# Sheet1.net
KiCad netlist of a schematic drawn in Altium Designer
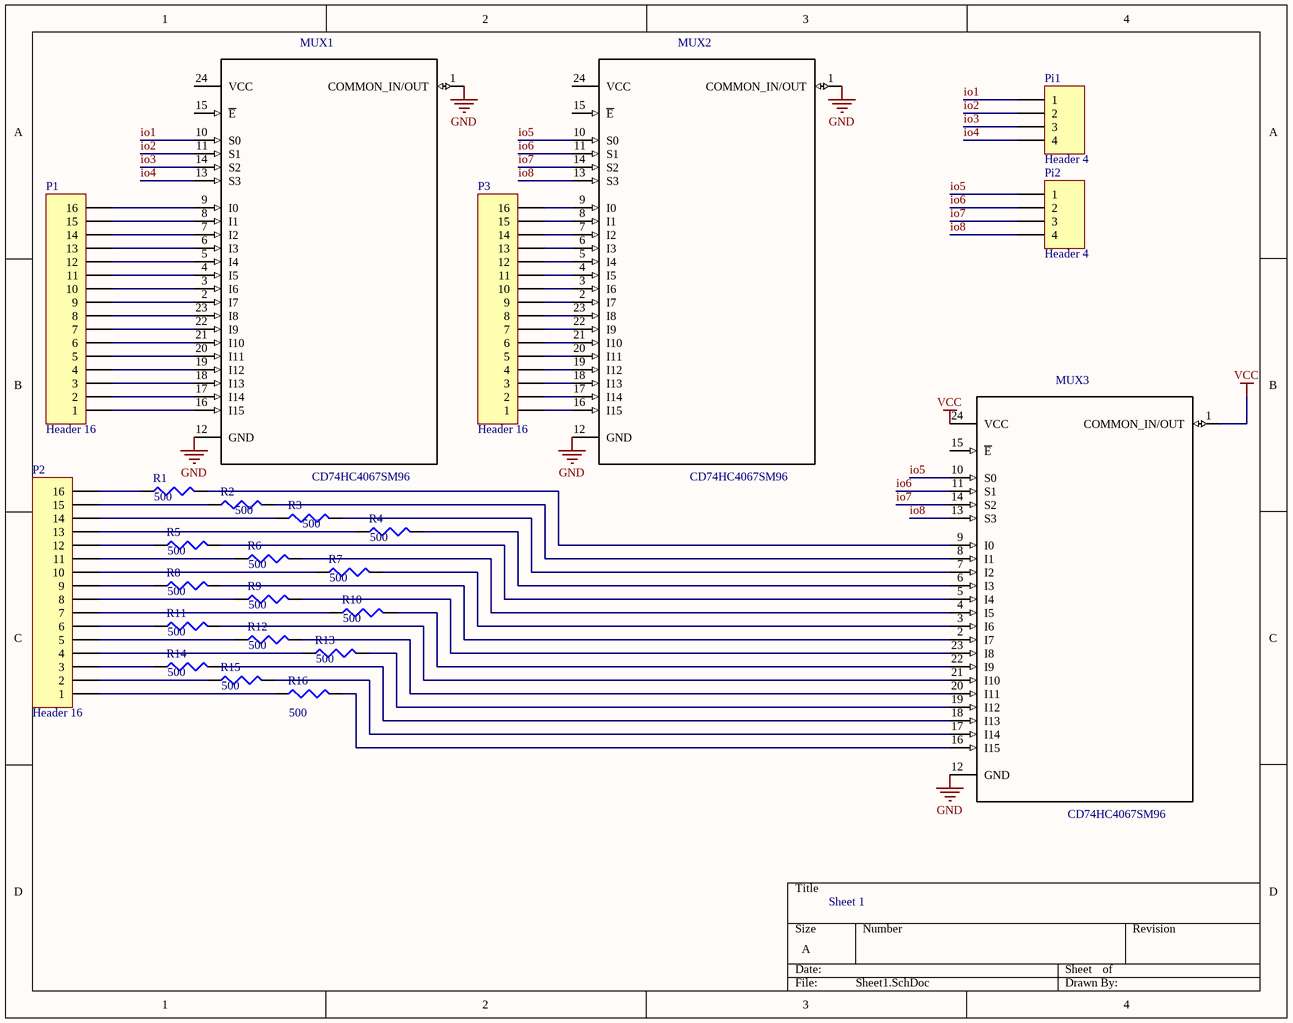
[diagram p0: Sheet1.SchDoc]

(export (version "E")
  (design (tool "Eeschema 10.0.6"))
  (components
    (comp (ref "MUX1")
      (value "CD74HC4067SM96")
      (footprint "SOP65P780X200-24N")
      (description "High Speed CMOS 16-Channel Analog Multiplexer/Demultiplexer 24-SSOP -55 to 125")
      (fields (field (name "MF") "Texas Instruments"))
      (libsource (lib "CD74HC4067SM96") (part "CD74HC4067SM96"))
    )
    (comp (ref "MUX2")
      (value "CD74HC4067SM96")
      (footprint "SOP65P780X200-24N")
      (description "High Speed CMOS 16-Channel Analog Multiplexer/Demultiplexer 24-SSOP -55 to 125")
      (fields (field (name "MF") "Texas Instruments"))
      (libsource (lib "CD74HC4067SM96") (part "CD74HC4067SM96"))
    )
    (comp (ref "MUX3")
      (value "CD74HC4067SM96")
      (footprint "SOP65P780X200-24N")
      (description "High Speed CMOS 16-Channel Analog Multiplexer/Demultiplexer 24-SSOP -55 to 125")
      (fields (field (name "MF") "Texas Instruments"))
      (libsource (lib "CD74HC4067SM96") (part "CD74HC4067SM96"))
    )
    (comp (ref "P1")
      (value "Header 16")
      (footprint "HDR1X16")
      (description "Header, 16-Pin")
      (fields (field (name "PUBLISHER") "Altium Limited"))
      (libsource (lib "Miscellaneous Connectors") (part "Header 16"))
    )
    (comp (ref "P2")
      (value "Header 16")
      (footprint "HDR1X16")
      (description "Header, 16-Pin")
      (fields (field (name "PUBLISHER") "Altium Limited"))
      (libsource (lib "Miscellaneous Connectors") (part "Header 16"))
    )
    (comp (ref "P3")
      (value "Header 16")
      (footprint "HDR1X16")
      (description "Header, 16-Pin")
      (fields (field (name "PUBLISHER") "Altium Limited"))
      (libsource (lib "Miscellaneous Connectors") (part "Header 16"))
    )
    (comp (ref "Pi1")
      (value "Header 4")
      (footprint "HDR1X4")
      (description "Header, 4-Pin")
      (fields (field (name "PUBLISHER") "Altium Limited"))
      (libsource (lib "Miscellaneous Connectors") (part "Header 4"))
    )
    (comp (ref "Pi2")
      (value "Header 4")
      (footprint "HDR1X4")
      (description "Header, 4-Pin")
      (fields (field (name "PUBLISHER") "Altium Limited"))
      (libsource (lib "Miscellaneous Connectors") (part "Header 4"))
    )
    (comp (ref "R1")
      (value "500")
      (footprint "J1-0603")
      (description "Resistor")
      (fields (field (name "Comment") "Res3") (field (name "PUBLISHER") "Altium Limited"))
      (libsource (lib "Miscellaneous Devices") (part "Res3"))
    )
    (comp (ref "R2")
      (value "500")
      (footprint "J1-0603")
      (description "Resistor")
      (fields (field (name "Comment") "Res3") (field (name "PUBLISHER") "Altium Limited"))
      (libsource (lib "Miscellaneous Devices") (part "Res3"))
    )
    (comp (ref "R3")
      (value "500")
      (footprint "J1-0603")
      (description "Resistor")
      (fields (field (name "Comment") "Res3") (field (name "PUBLISHER") "Altium Limited"))
      (libsource (lib "Miscellaneous Devices") (part "Res3"))
    )
    (comp (ref "R4")
      (value "500")
      (footprint "J1-0603")
      (description "Resistor")
      (fields (field (name "Comment") "Res3") (field (name "PUBLISHER") "Altium Limited"))
      (libsource (lib "Miscellaneous Devices") (part "Res3"))
    )
    (comp (ref "R5")
      (value "500")
      (footprint "J1-0603")
      (description "Resistor")
      (fields (field (name "Comment") "Res3") (field (name "PUBLISHER") "Altium Limited"))
      (libsource (lib "Miscellaneous Devices") (part "Res3"))
    )
    (comp (ref "R6")
      (value "500")
      (footprint "J1-0603")
      (description "Resistor")
      (fields (field (name "Comment") "Res3") (field (name "PUBLISHER") "Altium Limited"))
      (libsource (lib "Miscellaneous Devices") (part "Res3"))
    )
    (comp (ref "R7")
      (value "500")
      (footprint "J1-0603")
      (description "Resistor")
      (fields (field (name "Comment") "Res3") (field (name "PUBLISHER") "Altium Limited"))
      (libsource (lib "Miscellaneous Devices") (part "Res3"))
    )
    (comp (ref "R8")
      (value "500")
      (footprint "J1-0603")
      (description "Resistor")
      (fields (field (name "Comment") "Res3") (field (name "PUBLISHER") "Altium Limited"))
      (libsource (lib "Miscellaneous Devices") (part "Res3"))
    )
    (comp (ref "R9")
      (value "500")
      (footprint "J1-0603")
      (description "Resistor")
      (fields (field (name "Comment") "Res3") (field (name "PUBLISHER") "Altium Limited"))
      (libsource (lib "Miscellaneous Devices") (part "Res3"))
    )
    (comp (ref "R10")
      (value "500")
      (footprint "J1-0603")
      (description "Resistor")
      (fields (field (name "Comment") "Res3") (field (name "PUBLISHER") "Altium Limited"))
      (libsource (lib "Miscellaneous Devices") (part "Res3"))
    )
    (comp (ref "R11")
      (value "500")
      (footprint "J1-0603")
      (description "Resistor")
      (fields (field (name "Comment") "Res3") (field (name "PUBLISHER") "Altium Limited"))
      (libsource (lib "Miscellaneous Devices") (part "Res3"))
    )
    (comp (ref "R12")
      (value "500")
      (footprint "J1-0603")
      (description "Resistor")
      (fields (field (name "Comment") "Res3") (field (name "PUBLISHER") "Altium Limited"))
      (libsource (lib "Miscellaneous Devices") (part "Res3"))
    )
    (comp (ref "R13")
      (value "500")
      (footprint "J1-0603")
      (description "Resistor")
      (fields (field (name "Comment") "Res3") (field (name "PUBLISHER") "Altium Limited"))
      (libsource (lib "Miscellaneous Devices") (part "Res3"))
    )
    (comp (ref "R14")
      (value "500")
      (footprint "J1-0603")
      (description "Resistor")
      (fields (field (name "Comment") "Res3") (field (name "PUBLISHER") "Altium Limited"))
      (libsource (lib "Miscellaneous Devices") (part "Res3"))
    )
    (comp (ref "R15")
      (value "500")
      (footprint "J1-0603")
      (description "Resistor")
      (fields (field (name "Comment") "Res3") (field (name "PUBLISHER") "Altium Limited"))
      (libsource (lib "Miscellaneous Devices") (part "Res3"))
    )
    (comp (ref "R16")
      (value "500")
      (footprint "J1-0603")
      (description "Resistor")
      (fields (field (name "Comment") "Res3") (field (name "PUBLISHER") "Altium Limited"))
      (libsource (lib "Miscellaneous Devices") (part "Res3"))
    )
  )
  (nets
    (net (code "1") (name "/io1") (class "Default")
      (node (ref "MUX1") (pin "10") (pinfunction "S0_10") (pintype "input"))
      (node (ref "Pi1") (pin "1") (pinfunction "1_1") (pintype "passive"))
    )
    (net (code "2") (name "/io2") (class "Default")
      (node (ref "MUX1") (pin "11") (pinfunction "S1_11") (pintype "input"))
      (node (ref "Pi1") (pin "2") (pinfunction "2_2") (pintype "passive"))
    )
    (net (code "3") (name "/io3") (class "Default")
      (node (ref "MUX1") (pin "14") (pinfunction "S2_14") (pintype "input"))
      (node (ref "Pi1") (pin "3") (pinfunction "3_3") (pintype "passive"))
    )
    (net (code "4") (name "/io4") (class "Default")
      (node (ref "MUX1") (pin "13") (pinfunction "S3_13") (pintype "input"))
      (node (ref "Pi1") (pin "4") (pinfunction "4_4") (pintype "passive"))
    )
    (net (code "5") (name "/io5") (class "Default")
      (node (ref "MUX2") (pin "10") (pinfunction "S0_10") (pintype "input"))
      (node (ref "MUX3") (pin "10") (pinfunction "S0_10") (pintype "input"))
      (node (ref "Pi2") (pin "1") (pinfunction "1_1") (pintype "passive"))
    )
    (net (code "6") (name "/io6") (class "Default")
      (node (ref "MUX2") (pin "11") (pinfunction "S1_11") (pintype "input"))
      (node (ref "MUX3") (pin "11") (pinfunction "S1_11") (pintype "input"))
      (node (ref "Pi2") (pin "2") (pinfunction "2_2") (pintype "passive"))
    )
    (net (code "7") (name "/io7") (class "Default")
      (node (ref "MUX2") (pin "14") (pinfunction "S2_14") (pintype "input"))
      (node (ref "MUX3") (pin "14") (pinfunction "S2_14") (pintype "input"))
      (node (ref "Pi2") (pin "3") (pinfunction "3_3") (pintype "passive"))
    )
    (net (code "8") (name "/io8") (class "Default")
      (node (ref "MUX2") (pin "13") (pinfunction "S3_13") (pintype "input"))
      (node (ref "MUX3") (pin "13") (pinfunction "S3_13") (pintype "input"))
      (node (ref "Pi2") (pin "4") (pinfunction "4_4") (pintype "passive"))
    )
    (net (code "9") (name "GND") (class "Default")
      (node (ref "MUX1") (pin "1") (pinfunction "COMMON_IN/OUT_1") (pintype "bidirectional"))
      (node (ref "MUX1") (pin "12") (pinfunction "GND_12") (pintype "passive"))
      (node (ref "MUX2") (pin "1") (pinfunction "COMMON_IN/OUT_1") (pintype "bidirectional"))
      (node (ref "MUX2") (pin "12") (pinfunction "GND_12") (pintype "passive"))
      (node (ref "MUX3") (pin "12") (pinfunction "GND_12") (pintype "passive"))
    )
    (net (code "10") (name "Net-(MUX1-I0)") (class "Default")
      (node (ref "MUX1") (pin "9") (pinfunction "I0_9") (pintype "input"))
      (node (ref "P1") (pin "16") (pinfunction "16_16") (pintype "passive"))
    )
    (net (code "11") (name "Net-(MUX1-I1)") (class "Default")
      (node (ref "MUX1") (pin "8") (pinfunction "I1_8") (pintype "input"))
      (node (ref "P1") (pin "15") (pinfunction "15_15") (pintype "passive"))
    )
    (net (code "12") (name "Net-(MUX1-I2)") (class "Default")
      (node (ref "MUX1") (pin "7") (pinfunction "I2_7") (pintype "input"))
      (node (ref "P1") (pin "14") (pinfunction "14_14") (pintype "passive"))
    )
    (net (code "13") (name "Net-(MUX1-I3)") (class "Default")
      (node (ref "MUX1") (pin "6") (pinfunction "I3_6") (pintype "input"))
      (node (ref "P1") (pin "13") (pinfunction "13_13") (pintype "passive"))
    )
    (net (code "14") (name "Net-(MUX1-I4)") (class "Default")
      (node (ref "MUX1") (pin "5") (pinfunction "I4_5") (pintype "input"))
      (node (ref "P1") (pin "12") (pinfunction "12_12") (pintype "passive"))
    )
    (net (code "15") (name "Net-(MUX1-I5)") (class "Default")
      (node (ref "MUX1") (pin "4") (pinfunction "I5_4") (pintype "input"))
      (node (ref "P1") (pin "11") (pinfunction "11_11") (pintype "passive"))
    )
    (net (code "16") (name "Net-(MUX1-I6)") (class "Default")
      (node (ref "MUX1") (pin "3") (pinfunction "I6_3") (pintype "input"))
      (node (ref "P1") (pin "10") (pinfunction "10_10") (pintype "passive"))
    )
    (net (code "17") (name "Net-(MUX1-I7)") (class "Default")
      (node (ref "MUX1") (pin "2") (pinfunction "I7_2") (pintype "input"))
      (node (ref "P1") (pin "9") (pinfunction "9_9") (pintype "passive"))
    )
    (net (code "18") (name "Net-(MUX1-I8)") (class "Default")
      (node (ref "MUX1") (pin "23") (pinfunction "I8_23") (pintype "input"))
      (node (ref "P1") (pin "8") (pinfunction "8_8") (pintype "passive"))
    )
    (net (code "19") (name "Net-(MUX1-I9)") (class "Default")
      (node (ref "MUX1") (pin "22") (pinfunction "I9_22") (pintype "input"))
      (node (ref "P1") (pin "7") (pinfunction "7_7") (pintype "passive"))
    )
    (net (code "20") (name "Net-(MUX1-I10)") (class "Default")
      (node (ref "MUX1") (pin "21") (pinfunction "I10_21") (pintype "input"))
      (node (ref "P1") (pin "6") (pinfunction "6_6") (pintype "passive"))
    )
    (net (code "21") (name "Net-(MUX1-I11)") (class "Default")
      (node (ref "MUX1") (pin "20") (pinfunction "I11_20") (pintype "input"))
      (node (ref "P1") (pin "5") (pinfunction "5_5") (pintype "passive"))
    )
    (net (code "22") (name "Net-(MUX1-I12)") (class "Default")
      (node (ref "MUX1") (pin "19") (pinfunction "I12_19") (pintype "input"))
      (node (ref "P1") (pin "4") (pinfunction "4_4") (pintype "passive"))
    )
    (net (code "23") (name "Net-(MUX1-I13)") (class "Default")
      (node (ref "MUX1") (pin "18") (pinfunction "I13_18") (pintype "input"))
      (node (ref "P1") (pin "3") (pinfunction "3_3") (pintype "passive"))
    )
    (net (code "24") (name "Net-(MUX1-I14)") (class "Default")
      (node (ref "MUX1") (pin "17") (pinfunction "I14_17") (pintype "input"))
      (node (ref "P1") (pin "2") (pinfunction "2_2") (pintype "passive"))
    )
    (net (code "25") (name "Net-(MUX1-I15)") (class "Default")
      (node (ref "MUX1") (pin "16") (pinfunction "I15_16") (pintype "input"))
      (node (ref "P1") (pin "1") (pinfunction "1_1") (pintype "passive"))
    )
    (net (code "26") (name "Net-(MUX2-I0)") (class "Default")
      (node (ref "MUX2") (pin "9") (pinfunction "I0_9") (pintype "input"))
      (node (ref "P3") (pin "16") (pinfunction "16_16") (pintype "passive"))
    )
    (net (code "27") (name "Net-(MUX2-I1)") (class "Default")
      (node (ref "MUX2") (pin "8") (pinfunction "I1_8") (pintype "input"))
      (node (ref "P3") (pin "15") (pinfunction "15_15") (pintype "passive"))
    )
    (net (code "28") (name "Net-(MUX2-I2)") (class "Default")
      (node (ref "MUX2") (pin "7") (pinfunction "I2_7") (pintype "input"))
      (node (ref "P3") (pin "14") (pinfunction "14_14") (pintype "passive"))
    )
    (net (code "29") (name "Net-(MUX2-I3)") (class "Default")
      (node (ref "MUX2") (pin "6") (pinfunction "I3_6") (pintype "input"))
      (node (ref "P3") (pin "13") (pinfunction "13_13") (pintype "passive"))
    )
    (net (code "30") (name "Net-(MUX2-I4)") (class "Default")
      (node (ref "MUX2") (pin "5") (pinfunction "I4_5") (pintype "input"))
      (node (ref "P3") (pin "12") (pinfunction "12_12") (pintype "passive"))
    )
    (net (code "31") (name "Net-(MUX2-I5)") (class "Default")
      (node (ref "MUX2") (pin "4") (pinfunction "I5_4") (pintype "input"))
      (node (ref "P3") (pin "11") (pinfunction "11_11") (pintype "passive"))
    )
    (net (code "32") (name "Net-(MUX2-I6)") (class "Default")
      (node (ref "MUX2") (pin "3") (pinfunction "I6_3") (pintype "input"))
      (node (ref "P3") (pin "10") (pinfunction "10_10") (pintype "passive"))
    )
    (net (code "33") (name "Net-(MUX2-I7)") (class "Default")
      (node (ref "MUX2") (pin "2") (pinfunction "I7_2") (pintype "input"))
      (node (ref "P3") (pin "9") (pinfunction "9_9") (pintype "passive"))
    )
    (net (code "34") (name "Net-(MUX2-I8)") (class "Default")
      (node (ref "MUX2") (pin "23") (pinfunction "I8_23") (pintype "input"))
      (node (ref "P3") (pin "8") (pinfunction "8_8") (pintype "passive"))
    )
    (net (code "35") (name "Net-(MUX2-I9)") (class "Default")
      (node (ref "MUX2") (pin "22") (pinfunction "I9_22") (pintype "input"))
      (node (ref "P3") (pin "7") (pinfunction "7_7") (pintype "passive"))
    )
    (net (code "36") (name "Net-(MUX2-I10)") (class "Default")
      (node (ref "MUX2") (pin "21") (pinfunction "I10_21") (pintype "input"))
      (node (ref "P3") (pin "6") (pinfunction "6_6") (pintype "passive"))
    )
    (net (code "37") (name "Net-(MUX2-I11)") (class "Default")
      (node (ref "MUX2") (pin "20") (pinfunction "I11_20") (pintype "input"))
      (node (ref "P3") (pin "5") (pinfunction "5_5") (pintype "passive"))
    )
    (net (code "38") (name "Net-(MUX2-I12)") (class "Default")
      (node (ref "MUX2") (pin "19") (pinfunction "I12_19") (pintype "input"))
      (node (ref "P3") (pin "4") (pinfunction "4_4") (pintype "passive"))
    )
    (net (code "39") (name "Net-(MUX2-I13)") (class "Default")
      (node (ref "MUX2") (pin "18") (pinfunction "I13_18") (pintype "input"))
      (node (ref "P3") (pin "3") (pinfunction "3_3") (pintype "passive"))
    )
    (net (code "40") (name "Net-(MUX2-I14)") (class "Default")
      (node (ref "MUX2") (pin "17") (pinfunction "I14_17") (pintype "input"))
      (node (ref "P3") (pin "2") (pinfunction "2_2") (pintype "passive"))
    )
    (net (code "41") (name "Net-(MUX2-I15)") (class "Default")
      (node (ref "MUX2") (pin "16") (pinfunction "I15_16") (pintype "input"))
      (node (ref "P3") (pin "1") (pinfunction "1_1") (pintype "passive"))
    )
    (net (code "42") (name "Net-(MUX3-I0)") (class "Default")
      (node (ref "MUX3") (pin "9") (pinfunction "I0_9") (pintype "input"))
      (node (ref "R1") (pin "2") (pinfunction "2_2") (pintype "passive"))
    )
    (net (code "43") (name "Net-(MUX3-I1)") (class "Default")
      (node (ref "MUX3") (pin "8") (pinfunction "I1_8") (pintype "input"))
      (node (ref "R2") (pin "2") (pinfunction "2_2") (pintype "passive"))
    )
    (net (code "44") (name "Net-(MUX3-I2)") (class "Default")
      (node (ref "MUX3") (pin "7") (pinfunction "I2_7") (pintype "input"))
      (node (ref "R3") (pin "2") (pinfunction "2_2") (pintype "passive"))
    )
    (net (code "45") (name "Net-(MUX3-I3)") (class "Default")
      (node (ref "MUX3") (pin "6") (pinfunction "I3_6") (pintype "input"))
      (node (ref "R4") (pin "2") (pinfunction "2_2") (pintype "passive"))
    )
    (net (code "46") (name "Net-(MUX3-I4)") (class "Default")
      (node (ref "MUX3") (pin "5") (pinfunction "I4_5") (pintype "input"))
      (node (ref "R5") (pin "2") (pinfunction "2_2") (pintype "passive"))
    )
    (net (code "47") (name "Net-(MUX3-I5)") (class "Default")
      (node (ref "MUX3") (pin "4") (pinfunction "I5_4") (pintype "input"))
      (node (ref "R6") (pin "2") (pinfunction "2_2") (pintype "passive"))
    )
    (net (code "48") (name "Net-(MUX3-I6)") (class "Default")
      (node (ref "MUX3") (pin "3") (pinfunction "I6_3") (pintype "input"))
      (node (ref "R7") (pin "2") (pinfunction "2_2") (pintype "passive"))
    )
    (net (code "49") (name "Net-(MUX3-I7)") (class "Default")
      (node (ref "MUX3") (pin "2") (pinfunction "I7_2") (pintype "input"))
      (node (ref "R8") (pin "2") (pinfunction "2_2") (pintype "passive"))
    )
    (net (code "50") (name "Net-(MUX3-I8)") (class "Default")
      (node (ref "MUX3") (pin "23") (pinfunction "I8_23") (pintype "input"))
      (node (ref "R9") (pin "2") (pinfunction "2_2") (pintype "passive"))
    )
    (net (code "51") (name "Net-(MUX3-I9)") (class "Default")
      (node (ref "MUX3") (pin "22") (pinfunction "I9_22") (pintype "input"))
      (node (ref "R10") (pin "2") (pinfunction "2_2") (pintype "passive"))
    )
    (net (code "52") (name "Net-(MUX3-I10)") (class "Default")
      (node (ref "MUX3") (pin "21") (pinfunction "I10_21") (pintype "input"))
      (node (ref "R11") (pin "2") (pinfunction "2_2") (pintype "passive"))
    )
    (net (code "53") (name "Net-(MUX3-I11)") (class "Default")
      (node (ref "MUX3") (pin "20") (pinfunction "I11_20") (pintype "input"))
      (node (ref "R12") (pin "2") (pinfunction "2_2") (pintype "passive"))
    )
    (net (code "54") (name "Net-(MUX3-I12)") (class "Default")
      (node (ref "MUX3") (pin "19") (pinfunction "I12_19") (pintype "input"))
      (node (ref "R13") (pin "2") (pinfunction "2_2") (pintype "passive"))
    )
    (net (code "55") (name "Net-(MUX3-I13)") (class "Default")
      (node (ref "MUX3") (pin "18") (pinfunction "I13_18") (pintype "input"))
      (node (ref "R14") (pin "2") (pinfunction "2_2") (pintype "passive"))
    )
    (net (code "56") (name "Net-(MUX3-I14)") (class "Default")
      (node (ref "MUX3") (pin "17") (pinfunction "I14_17") (pintype "input"))
      (node (ref "R15") (pin "2") (pinfunction "2_2") (pintype "passive"))
    )
    (net (code "57") (name "Net-(MUX3-I15)") (class "Default")
      (node (ref "MUX3") (pin "16") (pinfunction "I15_16") (pintype "input"))
      (node (ref "R16") (pin "2") (pinfunction "2_2") (pintype "passive"))
    )
    (net (code "58") (name "Net-(P2-Pad1)") (class "Default")
      (node (ref "P2") (pin "1") (pinfunction "1_1") (pintype "passive"))
      (node (ref "R16") (pin "1") (pinfunction "1_1") (pintype "passive"))
    )
    (net (code "59") (name "Net-(P2-Pad2)") (class "Default")
      (node (ref "P2") (pin "2") (pinfunction "2_2") (pintype "passive"))
      (node (ref "R15") (pin "1") (pinfunction "1_1") (pintype "passive"))
    )
    (net (code "60") (name "Net-(P2-Pad3)") (class "Default")
      (node (ref "P2") (pin "3") (pinfunction "3_3") (pintype "passive"))
      (node (ref "R14") (pin "1") (pinfunction "1_1") (pintype "passive"))
    )
    (net (code "61") (name "Net-(P2-Pad4)") (class "Default")
      (node (ref "P2") (pin "4") (pinfunction "4_4") (pintype "passive"))
      (node (ref "R13") (pin "1") (pinfunction "1_1") (pintype "passive"))
    )
    (net (code "62") (name "Net-(P2-Pad5)") (class "Default")
      (node (ref "P2") (pin "5") (pinfunction "5_5") (pintype "passive"))
      (node (ref "R12") (pin "1") (pinfunction "1_1") (pintype "passive"))
    )
    (net (code "63") (name "Net-(P2-Pad6)") (class "Default")
      (node (ref "P2") (pin "6") (pinfunction "6_6") (pintype "passive"))
      (node (ref "R11") (pin "1") (pinfunction "1_1") (pintype "passive"))
    )
    (net (code "64") (name "Net-(P2-Pad7)") (class "Default")
      (node (ref "P2") (pin "7") (pinfunction "7_7") (pintype "passive"))
      (node (ref "R10") (pin "1") (pinfunction "1_1") (pintype "passive"))
    )
    (net (code "65") (name "Net-(P2-Pad8)") (class "Default")
      (node (ref "P2") (pin "8") (pinfunction "8_8") (pintype "passive"))
      (node (ref "R9") (pin "1") (pinfunction "1_1") (pintype "passive"))
    )
    (net (code "66") (name "Net-(P2-Pad9)") (class "Default")
      (node (ref "P2") (pin "9") (pinfunction "9_9") (pintype "passive"))
      (node (ref "R8") (pin "1") (pinfunction "1_1") (pintype "passive"))
    )
    (net (code "67") (name "Net-(P2-Pad10)") (class "Default")
      (node (ref "P2") (pin "10") (pinfunction "10_10") (pintype "passive"))
      (node (ref "R7") (pin "1") (pinfunction "1_1") (pintype "passive"))
    )
    (net (code "68") (name "Net-(P2-Pad11)") (class "Default")
      (node (ref "P2") (pin "11") (pinfunction "11_11") (pintype "passive"))
      (node (ref "R6") (pin "1") (pinfunction "1_1") (pintype "passive"))
    )
    (net (code "69") (name "Net-(P2-Pad12)") (class "Default")
      (node (ref "P2") (pin "12") (pinfunction "12_12") (pintype "passive"))
      (node (ref "R5") (pin "1") (pinfunction "1_1") (pintype "passive"))
    )
    (net (code "70") (name "Net-(P2-Pad13)") (class "Default")
      (node (ref "P2") (pin "13") (pinfunction "13_13") (pintype "passive"))
      (node (ref "R4") (pin "1") (pinfunction "1_1") (pintype "passive"))
    )
    (net (code "71") (name "Net-(P2-Pad14)") (class "Default")
      (node (ref "P2") (pin "14") (pinfunction "14_14") (pintype "passive"))
      (node (ref "R3") (pin "1") (pinfunction "1_1") (pintype "passive"))
    )
    (net (code "72") (name "Net-(P2-Pad15)") (class "Default")
      (node (ref "P2") (pin "15") (pinfunction "15_15") (pintype "passive"))
      (node (ref "R2") (pin "1") (pinfunction "1_1") (pintype "passive"))
    )
    (net (code "73") (name "Net-(P2-Pad16)") (class "Default")
      (node (ref "P2") (pin "16") (pinfunction "16_16") (pintype "passive"))
      (node (ref "R1") (pin "1") (pinfunction "1_1") (pintype "passive"))
    )
    (net (code "74") (name "VCC") (class "Default")
      (node (ref "MUX3") (pin "1") (pinfunction "COMMON_IN/OUT_1") (pintype "bidirectional"))
      (node (ref "MUX3") (pin "24") (pinfunction "VCC_24") (pintype "power_in"))
    )
    (net (code "75") (name "unconnected-(MUX1-VCC-Pad24)") (class "Default")
      (node (ref "MUX1") (pin "24") (pinfunction "VCC_24") (pintype "power_in"))
    )
    (net (code "76") (name "unconnected-(MUX1-~{E}-Pad15)") (class "Default")
      (node (ref "MUX1") (pin "15") (pinfunction "~{E}_15") (pintype "input"))
    )
    (net (code "77") (name "unconnected-(MUX2-VCC-Pad24)") (class "Default")
      (node (ref "MUX2") (pin "24") (pinfunction "VCC_24") (pintype "power_in"))
    )
    (net (code "78") (name "unconnected-(MUX2-~{E}-Pad15)") (class "Default")
      (node (ref "MUX2") (pin "15") (pinfunction "~{E}_15") (pintype "input"))
    )
    (net (code "79") (name "unconnected-(MUX3-~{E}-Pad15)") (class "Default")
      (node (ref "MUX3") (pin "15") (pinfunction "~{E}_15") (pintype "input"))
    )
  )
)
